# IS42S16400J.net
KiCad netlist of a schematic drawn in Altium Designer
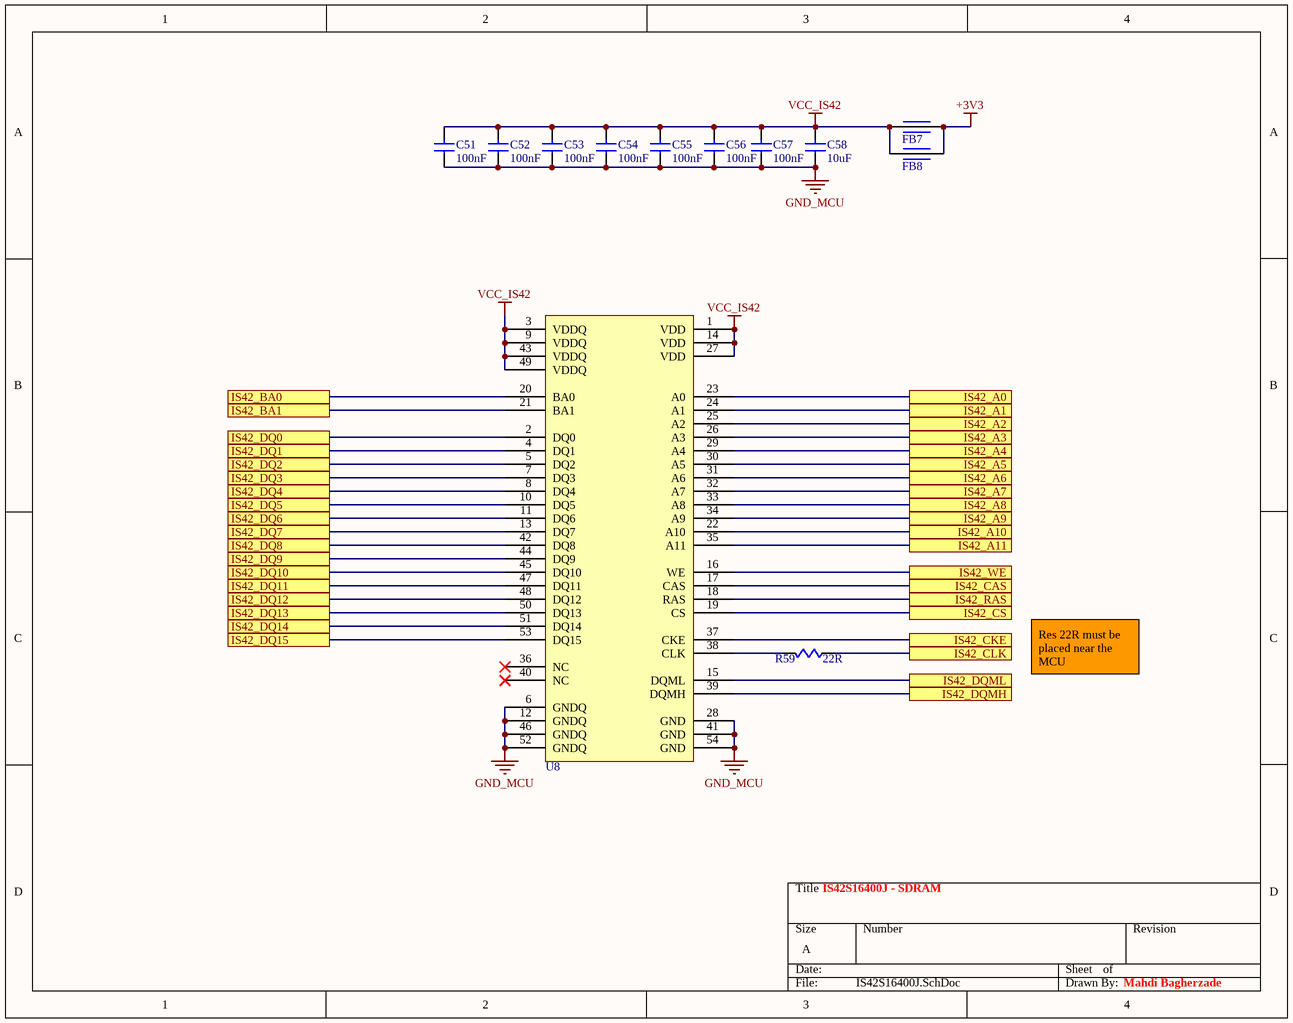
[diagram p0: IS42S16400J.SchDoc]

(export (version "E")
  (design (tool "Eeschema 10.0.6"))
  (components
    (comp (ref "C51")
      (value "100nF")
      (footprint "C-0805")
      (description "CAPACITOR")
      (fields
        (field (name "VOLTAGE") "50V")
        (field (name "TOLERANCE") "X7R")
        (field (name "PUBLISHER") "Mahdi Bagherzadeh")
      )
      (libsource (lib "Mahdi-Bagherzadeh") (part "CAP-CER"))
    )
    (comp (ref "C52")
      (value "100nF")
      (footprint "C-0805")
      (description "CAPACITOR")
      (fields
        (field (name "VOLTAGE") "50V")
        (field (name "TOLERANCE") "X7R")
        (field (name "PUBLISHER") "Mahdi Bagherzadeh")
      )
      (libsource (lib "Mahdi-Bagherzadeh") (part "CAP-CER"))
    )
    (comp (ref "C53")
      (value "100nF")
      (footprint "C-0805")
      (description "CAPACITOR")
      (fields
        (field (name "VOLTAGE") "50V")
        (field (name "TOLERANCE") "X7R")
        (field (name "PUBLISHER") "Mahdi Bagherzadeh")
      )
      (libsource (lib "Mahdi-Bagherzadeh") (part "CAP-CER"))
    )
    (comp (ref "C54")
      (value "100nF")
      (footprint "C-0805")
      (description "CAPACITOR")
      (fields
        (field (name "VOLTAGE") "50V")
        (field (name "TOLERANCE") "X7R")
        (field (name "PUBLISHER") "Mahdi Bagherzadeh")
      )
      (libsource (lib "Mahdi-Bagherzadeh") (part "CAP-CER"))
    )
    (comp (ref "C55")
      (value "100nF")
      (footprint "C-0805")
      (description "CAPACITOR")
      (fields
        (field (name "VOLTAGE") "50V")
        (field (name "TOLERANCE") "X7R")
        (field (name "PUBLISHER") "Mahdi Bagherzadeh")
      )
      (libsource (lib "Mahdi-Bagherzadeh") (part "CAP-CER"))
    )
    (comp (ref "C56")
      (value "100nF")
      (footprint "C-0805")
      (description "CAPACITOR")
      (fields
        (field (name "VOLTAGE") "50V")
        (field (name "TOLERANCE") "X7R")
        (field (name "PUBLISHER") "Mahdi Bagherzadeh")
      )
      (libsource (lib "Mahdi-Bagherzadeh") (part "CAP-CER"))
    )
    (comp (ref "C57")
      (value "100nF")
      (footprint "C-0805")
      (description "CAPACITOR")
      (fields
        (field (name "VOLTAGE") "50V")
        (field (name "TOLERANCE") "X7R")
        (field (name "PUBLISHER") "Mahdi Bagherzadeh")
      )
      (libsource (lib "Mahdi-Bagherzadeh") (part "CAP-CER"))
    )
    (comp (ref "C58")
      (value "10uF")
      (footprint "C-0805")
      (description "CAPACITOR")
      (fields
        (field (name "VOLTAGE") "50V")
        (field (name "TOLERANCE") "X7R")
        (field (name "PUBLISHER") "Mahdi Bagherzadeh")
      )
      (libsource (lib "Mahdi-Bagherzadeh") (part "CAP-CER"))
    )
    (comp (ref "FB7")
      (value "Ferrite Bead SMD")
      (footprint "FB-0805")
      (description "INDUCATOR")
      (fields (field (name "PUBLISHER") "Mahdi Bagherzadeh"))
      (libsource (lib "Mahdi-Bagherzadeh") (part "FERRITE BEAD"))
    )
    (comp (ref "FB8")
      (value "Ferrite Bead SMD")
      (footprint "FB-0805")
      (description "INDUCATOR")
      (fields (field (name "PUBLISHER") "Mahdi Bagherzadeh"))
      (libsource (lib "Mahdi-Bagherzadeh") (part "FERRITE BEAD"))
    )
    (comp (ref "R59")
      (value "22R")
      (footprint "R-0805")
      (description "RESISTOR")
      (fields
        (field (name "POWER") "1/8W")
        (field (name "TOLERANCE") "5%")
        (field (name "PUBLISHER") "Mahdi Bagherzadeh")
      )
      (libsource (lib "Mahdi-Bagherzadeh") (part "RES"))
    )
    (comp (ref "U8")
      (value "IC IS42S16400J-7TLI-SMD")
      (footprint "TSSOP-54")
      (description "IC")
      (fields (field (name "PUBLISHER") "Mahdi Bagherzadeh"))
      (libsource (lib "Mahdi-Bagherzadeh") (part "IS42S16400J-7TLI"))
    )
  )
  (nets
    (net (code "1") (name "+3V3") (class "Default")
      (node (ref "FB7") (pin "1") (pinfunction "1_1") (pintype "passive"))
      (node (ref "FB8") (pin "1") (pinfunction "1_1") (pintype "passive"))
    )
    (net (code "2") (name "/IS42_A0") (class "Default")
      (node (ref "U8") (pin "23") (pinfunction "A0_23") (pintype "passive"))
    )
    (net (code "3") (name "/IS42_A1") (class "Default")
      (node (ref "U8") (pin "24") (pinfunction "A1_24") (pintype "passive"))
    )
    (net (code "4") (name "/IS42_A2") (class "Default")
      (node (ref "U8") (pin "25") (pinfunction "A2_25") (pintype "passive"))
    )
    (net (code "5") (name "/IS42_A3") (class "Default")
      (node (ref "U8") (pin "26") (pinfunction "A3_26") (pintype "passive"))
    )
    (net (code "6") (name "/IS42_A4") (class "Default")
      (node (ref "U8") (pin "29") (pinfunction "A4_29") (pintype "passive"))
    )
    (net (code "7") (name "/IS42_A5") (class "Default")
      (node (ref "U8") (pin "30") (pinfunction "A5_30") (pintype "passive"))
    )
    (net (code "8") (name "/IS42_A6") (class "Default")
      (node (ref "U8") (pin "31") (pinfunction "A6_31") (pintype "passive"))
    )
    (net (code "9") (name "/IS42_A7") (class "Default")
      (node (ref "U8") (pin "32") (pinfunction "A7_32") (pintype "passive"))
    )
    (net (code "10") (name "/IS42_A8") (class "Default")
      (node (ref "U8") (pin "33") (pinfunction "A8_33") (pintype "passive"))
    )
    (net (code "11") (name "/IS42_A9") (class "Default")
      (node (ref "U8") (pin "34") (pinfunction "A9_34") (pintype "passive"))
    )
    (net (code "12") (name "/IS42_A10") (class "Default")
      (node (ref "U8") (pin "22") (pinfunction "A10_22") (pintype "passive"))
    )
    (net (code "13") (name "/IS42_A11") (class "Default")
      (node (ref "U8") (pin "35") (pinfunction "A11_35") (pintype "passive"))
    )
    (net (code "14") (name "/IS42_BA0") (class "Default")
      (node (ref "U8") (pin "20") (pinfunction "BA0_20") (pintype "passive"))
    )
    (net (code "15") (name "/IS42_BA1") (class "Default")
      (node (ref "U8") (pin "21") (pinfunction "BA1_21") (pintype "passive"))
    )
    (net (code "16") (name "/IS42_CAS") (class "Default")
      (node (ref "U8") (pin "17") (pinfunction "CAS_17") (pintype "passive"))
    )
    (net (code "17") (name "/IS42_CKE") (class "Default")
      (node (ref "U8") (pin "37") (pinfunction "CKE_37") (pintype "passive"))
    )
    (net (code "18") (name "/IS42_CLK") (class "Default")
      (node (ref "R59") (pin "1") (pinfunction "1_1") (pintype "passive"))
    )
    (net (code "19") (name "/IS42_CS") (class "Default")
      (node (ref "U8") (pin "19") (pinfunction "CS_19") (pintype "passive"))
    )
    (net (code "20") (name "/IS42_DQ0") (class "Default")
      (node (ref "U8") (pin "2") (pinfunction "DQ0_2") (pintype "passive"))
    )
    (net (code "21") (name "/IS42_DQ1") (class "Default")
      (node (ref "U8") (pin "4") (pinfunction "DQ1_4") (pintype "passive"))
    )
    (net (code "22") (name "/IS42_DQ2") (class "Default")
      (node (ref "U8") (pin "5") (pinfunction "DQ2_5") (pintype "passive"))
    )
    (net (code "23") (name "/IS42_DQ3") (class "Default")
      (node (ref "U8") (pin "7") (pinfunction "DQ3_7") (pintype "passive"))
    )
    (net (code "24") (name "/IS42_DQ4") (class "Default")
      (node (ref "U8") (pin "8") (pinfunction "DQ4_8") (pintype "passive"))
    )
    (net (code "25") (name "/IS42_DQ5") (class "Default")
      (node (ref "U8") (pin "10") (pinfunction "DQ5_10") (pintype "passive"))
    )
    (net (code "26") (name "/IS42_DQ6") (class "Default")
      (node (ref "U8") (pin "11") (pinfunction "DQ6_11") (pintype "passive"))
    )
    (net (code "27") (name "/IS42_DQ7") (class "Default")
      (node (ref "U8") (pin "13") (pinfunction "DQ7_13") (pintype "passive"))
    )
    (net (code "28") (name "/IS42_DQ8") (class "Default")
      (node (ref "U8") (pin "42") (pinfunction "DQ8_42") (pintype "passive"))
    )
    (net (code "29") (name "/IS42_DQ9") (class "Default")
      (node (ref "U8") (pin "44") (pinfunction "DQ9_44") (pintype "passive"))
    )
    (net (code "30") (name "/IS42_DQ10") (class "Default")
      (node (ref "U8") (pin "45") (pinfunction "DQ10_45") (pintype "passive"))
    )
    (net (code "31") (name "/IS42_DQ11") (class "Default")
      (node (ref "U8") (pin "47") (pinfunction "DQ11_47") (pintype "passive"))
    )
    (net (code "32") (name "/IS42_DQ12") (class "Default")
      (node (ref "U8") (pin "48") (pinfunction "DQ12_48") (pintype "passive"))
    )
    (net (code "33") (name "/IS42_DQ13") (class "Default")
      (node (ref "U8") (pin "50") (pinfunction "DQ13_50") (pintype "passive"))
    )
    (net (code "34") (name "/IS42_DQ14") (class "Default")
      (node (ref "U8") (pin "51") (pinfunction "DQ14_51") (pintype "passive"))
    )
    (net (code "35") (name "/IS42_DQ15") (class "Default")
      (node (ref "U8") (pin "53") (pinfunction "DQ15_53") (pintype "passive"))
    )
    (net (code "36") (name "/IS42_DQMH") (class "Default")
      (node (ref "U8") (pin "39") (pinfunction "DQMH_39") (pintype "passive"))
    )
    (net (code "37") (name "/IS42_DQML") (class "Default")
      (node (ref "U8") (pin "15") (pinfunction "DQML_15") (pintype "passive"))
    )
    (net (code "38") (name "/IS42_RAS") (class "Default")
      (node (ref "U8") (pin "18") (pinfunction "RAS_18") (pintype "passive"))
    )
    (net (code "39") (name "/IS42_WE") (class "Default")
      (node (ref "U8") (pin "16") (pinfunction "WE_16") (pintype "passive"))
    )
    (net (code "40") (name "GND_MCU") (class "Default")
      (node (ref "C51") (pin "1") (pinfunction "1_1") (pintype "passive"))
      (node (ref "C52") (pin "1") (pinfunction "1_1") (pintype "passive"))
      (node (ref "C53") (pin "1") (pinfunction "1_1") (pintype "passive"))
      (node (ref "C54") (pin "1") (pinfunction "1_1") (pintype "passive"))
      (node (ref "C55") (pin "1") (pinfunction "1_1") (pintype "passive"))
      (node (ref "C56") (pin "1") (pinfunction "1_1") (pintype "passive"))
      (node (ref "C57") (pin "1") (pinfunction "1_1") (pintype "passive"))
      (node (ref "C58") (pin "1") (pinfunction "1_1") (pintype "passive"))
      (node (ref "U8") (pin "12") (pinfunction "GNDQ_12") (pintype "passive"))
      (node (ref "U8") (pin "28") (pinfunction "GND_28") (pintype "passive"))
      (node (ref "U8") (pin "41") (pinfunction "GND_41") (pintype "passive"))
      (node (ref "U8") (pin "46") (pinfunction "GNDQ_46") (pintype "passive"))
      (node (ref "U8") (pin "52") (pinfunction "GNDQ_52") (pintype "passive"))
      (node (ref "U8") (pin "54") (pinfunction "GND_54") (pintype "passive"))
      (node (ref "U8") (pin "6") (pinfunction "GNDQ_6") (pintype "passive"))
    )
    (net (code "41") (name "Net-(U8-CLK)") (class "Default")
      (node (ref "R59") (pin "2") (pinfunction "2_2") (pintype "passive"))
      (node (ref "U8") (pin "38") (pinfunction "CLK_38") (pintype "passive"))
    )
    (net (code "42") (name "VCC_IS42") (class "Default")
      (node (ref "C51") (pin "2") (pinfunction "2_2") (pintype "passive"))
      (node (ref "C52") (pin "2") (pinfunction "2_2") (pintype "passive"))
      (node (ref "C53") (pin "2") (pinfunction "2_2") (pintype "passive"))
      (node (ref "C54") (pin "2") (pinfunction "2_2") (pintype "passive"))
      (node (ref "C55") (pin "2") (pinfunction "2_2") (pintype "passive"))
      (node (ref "C56") (pin "2") (pinfunction "2_2") (pintype "passive"))
      (node (ref "C57") (pin "2") (pinfunction "2_2") (pintype "passive"))
      (node (ref "C58") (pin "2") (pinfunction "2_2") (pintype "passive"))
      (node (ref "FB7") (pin "2") (pinfunction "2_2") (pintype "passive"))
      (node (ref "FB8") (pin "2") (pinfunction "2_2") (pintype "passive"))
      (node (ref "U8") (pin "1") (pinfunction "VDD_1") (pintype "passive"))
      (node (ref "U8") (pin "14") (pinfunction "VDD_14") (pintype "passive"))
      (node (ref "U8") (pin "27") (pinfunction "VDD_27") (pintype "passive"))
      (node (ref "U8") (pin "3") (pinfunction "VDDQ_3") (pintype "passive"))
      (node (ref "U8") (pin "43") (pinfunction "VDDQ_43") (pintype "passive"))
      (node (ref "U8") (pin "49") (pinfunction "VDDQ_49") (pintype "passive"))
      (node (ref "U8") (pin "9") (pinfunction "VDDQ_9") (pintype "passive"))
    )
    (net (code "43") (name "unconnected-(U8-NC-Pad36)") (class "Default")
      (node (ref "U8") (pin "36") (pinfunction "NC_36") (pintype "passive+no_connect"))
    )
    (net (code "44") (name "unconnected-(U8-NC-Pad40)") (class "Default")
      (node (ref "U8") (pin "40") (pinfunction "NC_40") (pintype "passive+no_connect"))
    )
  )
)
